# Sheet1.net
KiCad netlist of a schematic drawn in Altium Designer
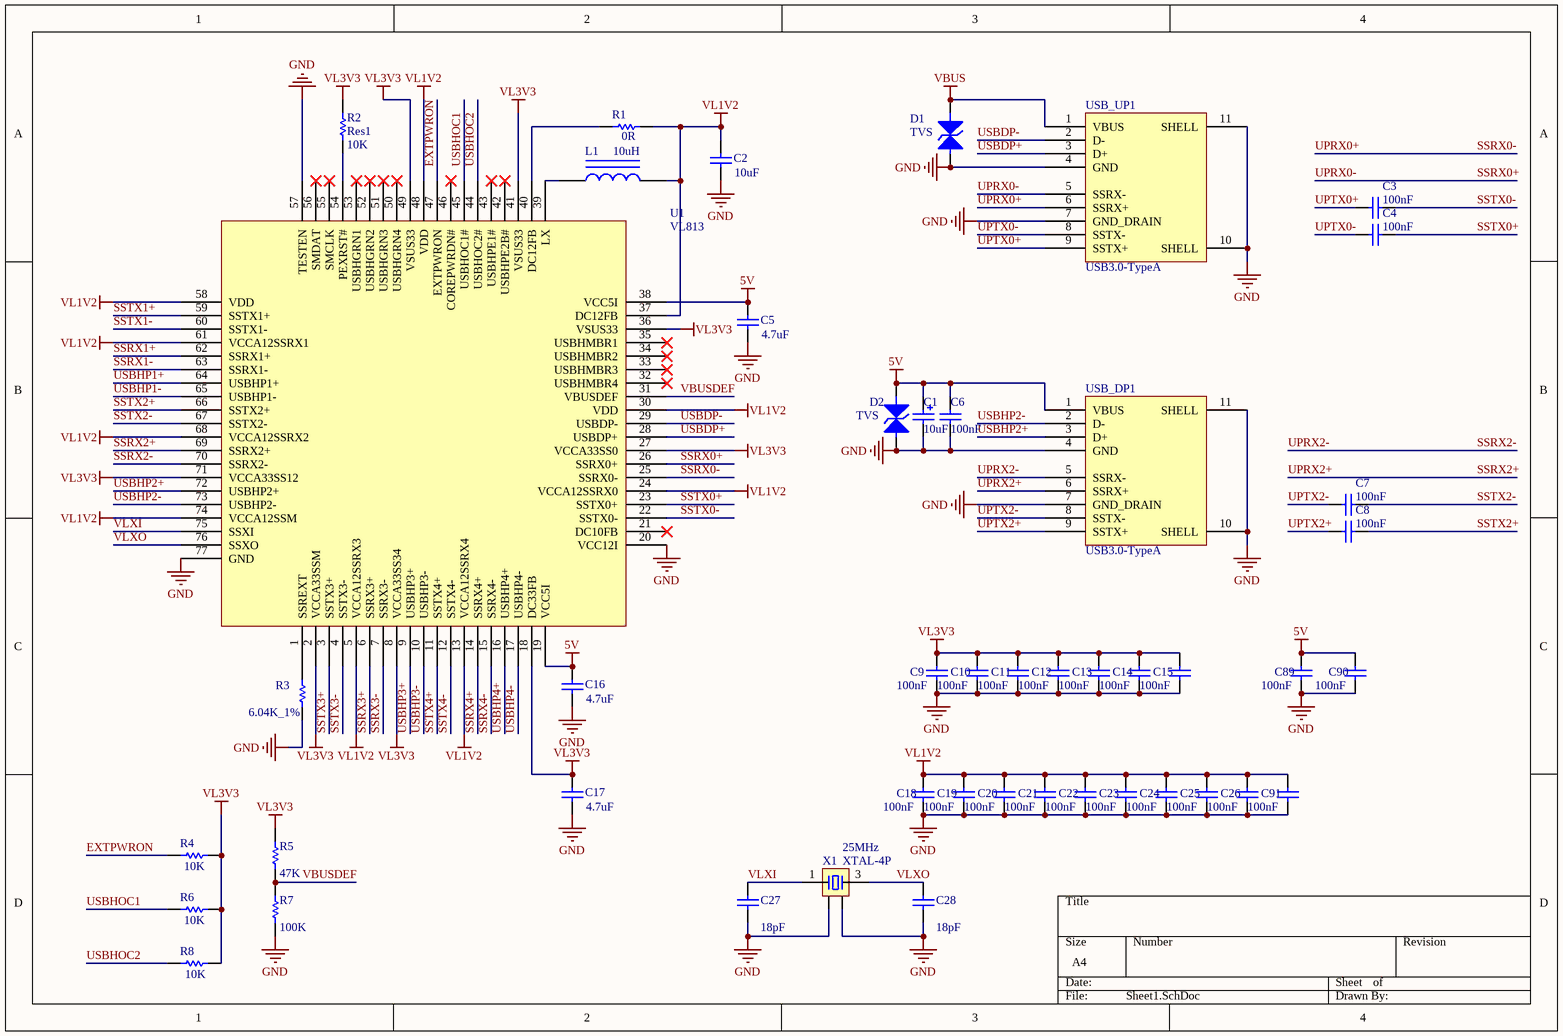
[diagram p0: Sheet1.SchDoc]

(export (version "E")
  (design (tool "Eeschema 10.0.6"))
  (components
    (comp (ref "C1")
      (value "10uF")
      (footprint "电容:TAJ-A/3216")
      (description "Polarized Capacitor (Axial)")
      (fields (field (name "Comment") "Cap Pol2") (field (name "PUBLISHER") "Altium Limited"))
      (libsource (lib "Miscellaneous Devices") (part "Cap Pol2"))
    )
    (comp (ref "C2")
      (value "10uF")
      (footprint "C0603_M")
      (description "Capacitor")
      (fields (field (name "Comment") "Cap") (field (name "PUBLISHER") "Altium Limited"))
      (libsource (lib "Miscellaneous Devices") (part "Cap"))
    )
    (comp (ref "C3")
      (value "100nF")
      (footprint "1.03-电容:C0402_M")
      (description "Capacitor")
      (fields (field (name "Comment") "Cap") (field (name "PUBLISHER") "Altium Limited"))
      (libsource (lib "Miscellaneous Devices") (part "Cap"))
    )
    (comp (ref "C4")
      (value "100nF")
      (footprint "1.03-电容:C0402_M")
      (description "Capacitor")
      (fields (field (name "Comment") "Cap") (field (name "PUBLISHER") "Altium Limited"))
      (libsource (lib "Miscellaneous Devices") (part "Cap"))
    )
    (comp (ref "C5")
      (value "4.7uF")
      (footprint "C0603_M")
      (description "Capacitor")
      (fields (field (name "Comment") "Cap") (field (name "PUBLISHER") "Altium Limited"))
      (libsource (lib "Miscellaneous Devices") (part "Cap"))
    )
    (comp (ref "C6")
      (value "100nF")
      (footprint "C0603_M")
      (description "Capacitor")
      (fields (field (name "Comment") "Cap") (field (name "PUBLISHER") "Altium Limited"))
      (libsource (lib "Miscellaneous Devices") (part "Cap"))
    )
    (comp (ref "C7")
      (value "100nF")
      (footprint "1.03-电容:C0402_M")
      (description "Capacitor")
      (fields (field (name "Comment") "Cap") (field (name "PUBLISHER") "Altium Limited"))
      (libsource (lib "Miscellaneous Devices") (part "Cap"))
    )
    (comp (ref "C8")
      (value "100nF")
      (footprint "1.03-电容:C0402_M")
      (description "Capacitor")
      (fields (field (name "Comment") "Cap") (field (name "PUBLISHER") "Altium Limited"))
      (libsource (lib "Miscellaneous Devices") (part "Cap"))
    )
    (comp (ref "C9")
      (value "100nF")
      (footprint "1.03-电容:C0603_M")
      (description "Capacitor")
      (fields (field (name "Comment") "Cap") (field (name "PUBLISHER") "Altium Limited"))
      (libsource (lib "Miscellaneous Devices") (part "Cap"))
    )
    (comp (ref "C10")
      (value "100nF")
      (footprint "C0603_M")
      (description "Capacitor")
      (fields (field (name "Comment") "Cap") (field (name "PUBLISHER") "Altium Limited"))
      (libsource (lib "Miscellaneous Devices") (part "Cap"))
    )
    (comp (ref "C11")
      (value "100nF")
      (footprint "C0603_M")
      (description "Capacitor")
      (fields (field (name "Comment") "Cap") (field (name "PUBLISHER") "Altium Limited"))
      (libsource (lib "Miscellaneous Devices") (part "Cap"))
    )
    (comp (ref "C12")
      (value "100nF")
      (footprint "C0603_M")
      (description "Capacitor")
      (fields (field (name "Comment") "Cap") (field (name "PUBLISHER") "Altium Limited"))
      (libsource (lib "Miscellaneous Devices") (part "Cap"))
    )
    (comp (ref "C13")
      (value "100nF")
      (footprint "C0603_M")
      (description "Capacitor")
      (fields (field (name "Comment") "Cap") (field (name "PUBLISHER") "Altium Limited"))
      (libsource (lib "Miscellaneous Devices") (part "Cap"))
    )
    (comp (ref "C14")
      (value "100nF")
      (footprint "C0603_M")
      (description "Capacitor")
      (fields (field (name "Comment") "Cap") (field (name "PUBLISHER") "Altium Limited"))
      (libsource (lib "Miscellaneous Devices") (part "Cap"))
    )
    (comp (ref "C15")
      (value "100nF")
      (footprint "C0603_M")
      (description "Capacitor")
      (fields (field (name "Comment") "Cap") (field (name "PUBLISHER") "Altium Limited"))
      (libsource (lib "Miscellaneous Devices") (part "Cap"))
    )
    (comp (ref "C16")
      (value "4.7uF")
      (footprint "C0603_M")
      (description "Capacitor")
      (fields (field (name "Comment") "Cap") (field (name "PUBLISHER") "Altium Limited"))
      (libsource (lib "Miscellaneous Devices") (part "Cap"))
    )
    (comp (ref "C17")
      (value "4.7uF")
      (footprint "C0603_M")
      (description "Capacitor")
      (fields (field (name "Comment") "Cap") (field (name "PUBLISHER") "Altium Limited"))
      (libsource (lib "Miscellaneous Devices") (part "Cap"))
    )
    (comp (ref "C18")
      (value "100nF")
      (footprint "C0603_M")
      (description "Capacitor")
      (fields (field (name "Comment") "Cap") (field (name "PUBLISHER") "Altium Limited"))
      (libsource (lib "Miscellaneous Devices") (part "Cap"))
    )
    (comp (ref "C19")
      (value "100nF")
      (footprint "C0603_M")
      (description "Capacitor")
      (fields (field (name "Comment") "Cap") (field (name "PUBLISHER") "Altium Limited"))
      (libsource (lib "Miscellaneous Devices") (part "Cap"))
    )
    (comp (ref "C20")
      (value "100nF")
      (footprint "C0603_M")
      (description "Capacitor")
      (fields (field (name "Comment") "Cap") (field (name "PUBLISHER") "Altium Limited"))
      (libsource (lib "Miscellaneous Devices") (part "Cap"))
    )
    (comp (ref "C21")
      (value "100nF")
      (footprint "C0603_M")
      (description "Capacitor")
      (fields (field (name "Comment") "Cap") (field (name "PUBLISHER") "Altium Limited"))
      (libsource (lib "Miscellaneous Devices") (part "Cap"))
    )
    (comp (ref "C22")
      (value "100nF")
      (footprint "C0603_M")
      (description "Capacitor")
      (fields (field (name "Comment") "Cap") (field (name "PUBLISHER") "Altium Limited"))
      (libsource (lib "Miscellaneous Devices") (part "Cap"))
    )
    (comp (ref "C23")
      (value "100nF")
      (footprint "C0603_M")
      (description "Capacitor")
      (fields (field (name "Comment") "Cap") (field (name "PUBLISHER") "Altium Limited"))
      (libsource (lib "Miscellaneous Devices") (part "Cap"))
    )
    (comp (ref "C24")
      (value "100nF")
      (footprint "C0603_M")
      (description "Capacitor")
      (fields (field (name "Comment") "Cap") (field (name "PUBLISHER") "Altium Limited"))
      (libsource (lib "Miscellaneous Devices") (part "Cap"))
    )
    (comp (ref "C25")
      (value "100nF")
      (footprint "C0603_M")
      (description "Capacitor")
      (fields (field (name "Comment") "Cap") (field (name "PUBLISHER") "Altium Limited"))
      (libsource (lib "Miscellaneous Devices") (part "Cap"))
    )
    (comp (ref "C26")
      (value "100nF")
      (footprint "C0603_M")
      (description "Capacitor")
      (fields (field (name "Comment") "Cap") (field (name "PUBLISHER") "Altium Limited"))
      (libsource (lib "Miscellaneous Devices") (part "Cap"))
    )
    (comp (ref "C27")
      (value "18pF")
      (footprint "C0603_M")
      (description "Capacitor")
      (fields (field (name "Comment") "Cap") (field (name "PUBLISHER") "Altium Limited"))
      (libsource (lib "Miscellaneous Devices") (part "Cap"))
    )
    (comp (ref "C28")
      (value "18pF")
      (footprint "C0603_M")
      (description "Capacitor")
      (fields (field (name "Comment") "Cap") (field (name "PUBLISHER") "Altium Limited"))
      (libsource (lib "Miscellaneous Devices") (part "Cap"))
    )
    (comp (ref "C89")
      (value "100nF")
      (footprint "C0603_M")
      (description "Capacitor")
      (fields (field (name "Comment") "Cap") (field (name "PUBLISHER") "Altium Limited"))
      (libsource (lib "Miscellaneous Devices") (part "Cap"))
    )
    (comp (ref "C90")
      (value "100nF")
      (footprint "C0603_M")
      (description "Capacitor")
      (fields (field (name "Comment") "Cap") (field (name "PUBLISHER") "Altium Limited"))
      (libsource (lib "Miscellaneous Devices") (part "Cap"))
    )
    (comp (ref "C91")
      (value "100nF")
      (footprint "C0603_M")
      (description "Capacitor")
      (fields (field (name "Comment") "Cap") (field (name "PUBLISHER") "Altium Limited"))
      (libsource (lib "Miscellaneous Devices") (part "Cap"))
    )
    (comp (ref "D1")
      (value "TVS")
      (footprint "二极管:SOD-123")
      (description "双向瞬态抑制二极管")
      (libsource (lib "二极管") (part "TVS"))
    )
    (comp (ref "D2")
      (value "TVS")
      (footprint "二极管:SOD-123")
      (description "双向瞬态抑制二极管")
      (libsource (lib "二极管") (part "TVS"))
    )
    (comp (ref "L1")
      (value "10uH")
      (footprint "1.04-电感:SWPA3012")
      (description "Magnetic-Core Inductor")
      (fields (field (name "Comment") "Inductor Iron") (field (name "PUBLISHER") "Altium Limited"))
      (libsource (lib "Miscellaneous Devices") (part "Inductor Iron"))
    )
    (comp (ref "R1")
      (value "0R")
      (footprint "R0603_M")
      (description "Resistor")
      (fields (field (name "Comment") "Res1") (field (name "PUBLISHER") "Altium Limited"))
      (libsource (lib "Miscellaneous Devices") (part "Res1"))
    )
    (comp (ref "R2")
      (value "Res1")
      (footprint "R0603_M")
      (description "Resistor")
      (fields (field (name "ALTIUM_VALUE") "10K") (field (name "PUBLISHER") "Altium Limited"))
      (libsource (lib "Miscellaneous Devices") (part "Res1"))
    )
    (comp (ref "R3")
      (value "6.04K_1%")
      (footprint "R0603_M")
      (description "Resistor")
      (fields (field (name "Comment") "Res1") (field (name "PUBLISHER") "Altium Limited"))
      (libsource (lib "Miscellaneous Devices") (part "Res1"))
    )
    (comp (ref "R4")
      (value "10K")
      (footprint "R0603_M")
      (description "Resistor")
      (fields (field (name "Comment") "Res1") (field (name "PUBLISHER") "Altium Limited"))
      (libsource (lib "Miscellaneous Devices") (part "Res1"))
    )
    (comp (ref "R5")
      (value "47K")
      (footprint "R0603_M")
      (description "Resistor")
      (fields (field (name "Comment") "Res1") (field (name "PUBLISHER") "Altium Limited"))
      (libsource (lib "Miscellaneous Devices") (part "Res1"))
    )
    (comp (ref "R6")
      (value "10K")
      (footprint "R0603_M")
      (description "Resistor")
      (fields (field (name "Comment") "Res1") (field (name "PUBLISHER") "Altium Limited"))
      (libsource (lib "Miscellaneous Devices") (part "Res1"))
    )
    (comp (ref "R7")
      (value "100K")
      (footprint "R0603_M")
      (description "Resistor")
      (fields (field (name "Comment") "Res1") (field (name "PUBLISHER") "Altium Limited"))
      (libsource (lib "Miscellaneous Devices") (part "Res1"))
    )
    (comp (ref "R8")
      (value "10K")
      (footprint "R0603_M")
      (description "Resistor")
      (fields (field (name "Comment") "Res1") (field (name "PUBLISHER") "Altium Limited"))
      (libsource (lib "Miscellaneous Devices") (part "Res1"))
    )
    (comp (ref "U1")
      (value "VL813")
      (footprint "QFN-76_L9.0-W9.0")
      (description "USB3.0 Hub")
      (libsource (lib "MyIntLib") (part "VL813"))
    )
    (comp (ref "USB_DP1")
      (value "USB3.0-TypeA")
      (footprint "3.03-USB3.1 Type C-M.2-NGFF-HDMI-PCI-E接口:USB3.1 Type-A_DIP_F")
      (libsource (lib "MyIntLib") (part "USB3.0-TypeA"))
    )
    (comp (ref "USB_UP1")
      (value "USB3.0-TypeA")
      (footprint "3.03-USB3.1 Type C-M.2-NGFF-HDMI-PCI-E接口:USB3.1 Type-A_DIP_F")
      (libsource (lib "MyIntLib") (part "USB3.0-TypeA"))
    )
    (comp (ref "X1")
      (value "XTAL-4P")
      (footprint "OSC 3225-4P")
      (description "4脚无源晶振")
      (fields (field (name "PARAMETER 1") "25MHz"))
      (libsource (lib "晶振") (part "XTAL-4P"))
    )
  )
  (nets
    (net (code "1") (name "/EXTPWRON") (class "Default")
      (node (ref "R4") (pin "2") (pinfunction "2_2") (pintype "passive"))
      (node (ref "U1") (pin "47") (pinfunction "EXTPWRON_47") (pintype "passive"))
    )
    (net (code "2") (name "/SSRX0+") (class "Default")
      (node (ref "U1") (pin "26") (pinfunction "SSRX0+_26") (pintype "passive"))
      (node (ref "USB_UP1") (pin "5") (pinfunction "SSRX-_5") (pintype "passive"))
    )
    (net (code "3") (name "/SSRX0-") (class "Default")
      (node (ref "U1") (pin "25") (pinfunction "SSRX0-_25") (pintype "passive"))
      (node (ref "USB_UP1") (pin "6") (pinfunction "SSRX+_6") (pintype "passive"))
    )
    (net (code "4") (name "/SSRX1+") (class "Default")
      (node (ref "U1") (pin "62") (pinfunction "SSRX1+_62") (pintype "passive"))
    )
    (net (code "5") (name "/SSRX1-") (class "Default")
      (node (ref "U1") (pin "63") (pinfunction "SSRX1-_63") (pintype "passive"))
    )
    (net (code "6") (name "/SSRX2+") (class "Default")
      (node (ref "U1") (pin "69") (pinfunction "SSRX2+_69") (pintype "passive"))
      (node (ref "USB_DP1") (pin "6") (pinfunction "SSRX+_6") (pintype "passive"))
    )
    (net (code "7") (name "/SSRX2-") (class "Default")
      (node (ref "U1") (pin "70") (pinfunction "SSRX2-_70") (pintype "passive"))
      (node (ref "USB_DP1") (pin "5") (pinfunction "SSRX-_5") (pintype "passive"))
    )
    (net (code "8") (name "/SSRX3+") (class "Default")
      (node (ref "U1") (pin "6") (pinfunction "SSRX3+_6") (pintype "passive"))
    )
    (net (code "9") (name "/SSRX3-") (class "Default")
      (node (ref "U1") (pin "7") (pinfunction "SSRX3-_7") (pintype "passive"))
    )
    (net (code "10") (name "/SSRX4+") (class "Default")
      (node (ref "U1") (pin "14") (pinfunction "SSRX4+_14") (pintype "passive"))
    )
    (net (code "11") (name "/SSRX4-") (class "Default")
      (node (ref "U1") (pin "15") (pinfunction "SSRX4-_15") (pintype "passive"))
    )
    (net (code "12") (name "/SSTX0+") (class "Default")
      (node (ref "C4") (pin "1") (pinfunction "1_1") (pintype "passive"))
      (node (ref "U1") (pin "23") (pinfunction "SSTX0+_23") (pintype "passive"))
    )
    (net (code "13") (name "/SSTX0-") (class "Default")
      (node (ref "C3") (pin "1") (pinfunction "1_1") (pintype "passive"))
      (node (ref "U1") (pin "22") (pinfunction "SSTX0-_22") (pintype "passive"))
    )
    (net (code "14") (name "/SSTX1+") (class "Default")
      (node (ref "U1") (pin "59") (pinfunction "SSTX1+_59") (pintype "passive"))
    )
    (net (code "15") (name "/SSTX1-") (class "Default")
      (node (ref "U1") (pin "60") (pinfunction "SSTX1-_60") (pintype "passive"))
    )
    (net (code "16") (name "/SSTX2+") (class "Default")
      (node (ref "C8") (pin "1") (pinfunction "1_1") (pintype "passive"))
      (node (ref "U1") (pin "66") (pinfunction "SSTX2+_66") (pintype "passive"))
    )
    (net (code "17") (name "/SSTX2-") (class "Default")
      (node (ref "C7") (pin "1") (pinfunction "1_1") (pintype "passive"))
      (node (ref "U1") (pin "67") (pinfunction "SSTX2-_67") (pintype "passive"))
    )
    (net (code "18") (name "/SSTX3+") (class "Default")
      (node (ref "U1") (pin "3") (pinfunction "SSTX3+_3") (pintype "passive"))
    )
    (net (code "19") (name "/SSTX3-") (class "Default")
      (node (ref "U1") (pin "4") (pinfunction "SSTX3-_4") (pintype "passive"))
    )
    (net (code "20") (name "/SSTX4+") (class "Default")
      (node (ref "U1") (pin "11") (pinfunction "SSTX4+_11") (pintype "passive"))
    )
    (net (code "21") (name "/SSTX4-") (class "Default")
      (node (ref "U1") (pin "12") (pinfunction "SSTX4-_12") (pintype "passive"))
    )
    (net (code "22") (name "/UPTX0+") (class "Default")
      (node (ref "C3") (pin "2") (pinfunction "2_2") (pintype "passive"))
      (node (ref "USB_UP1") (pin "9") (pinfunction "SSTX+_9") (pintype "passive"))
    )
    (net (code "23") (name "/UPTX0-") (class "Default")
      (node (ref "C4") (pin "2") (pinfunction "2_2") (pintype "passive"))
      (node (ref "USB_UP1") (pin "8") (pinfunction "SSTX-_8") (pintype "passive"))
    )
    (net (code "24") (name "/UPTX2+") (class "Default")
      (node (ref "C8") (pin "2") (pinfunction "2_2") (pintype "passive"))
      (node (ref "USB_DP1") (pin "9") (pinfunction "SSTX+_9") (pintype "passive"))
    )
    (net (code "25") (name "/UPTX2-") (class "Default")
      (node (ref "C7") (pin "2") (pinfunction "2_2") (pintype "passive"))
      (node (ref "USB_DP1") (pin "8") (pinfunction "SSTX-_8") (pintype "passive"))
    )
    (net (code "26") (name "/USBDP+") (class "Default")
      (node (ref "U1") (pin "28") (pinfunction "USBDP+_28") (pintype "passive"))
      (node (ref "USB_UP1") (pin "3") (pinfunction "D+_3") (pintype "passive"))
    )
    (net (code "27") (name "/USBDP-") (class "Default")
      (node (ref "U1") (pin "29") (pinfunction "USBDP-_29") (pintype "passive"))
      (node (ref "USB_UP1") (pin "2") (pinfunction "D-_2") (pintype "passive"))
    )
    (net (code "28") (name "/USBHOC1") (class "Default")
      (node (ref "R6") (pin "2") (pinfunction "2_2") (pintype "passive"))
      (node (ref "U1") (pin "45") (pinfunction "USBHOC1#_45") (pintype "passive"))
    )
    (net (code "29") (name "/USBHOC2") (class "Default")
      (node (ref "R8") (pin "2") (pinfunction "2_2") (pintype "passive"))
      (node (ref "U1") (pin "44") (pinfunction "USBHOC2#_44") (pintype "passive"))
    )
    (net (code "30") (name "/USBHP1+") (class "Default")
      (node (ref "U1") (pin "64") (pinfunction "USBHP1+_64") (pintype "passive"))
    )
    (net (code "31") (name "/USBHP1-") (class "Default")
      (node (ref "U1") (pin "65") (pinfunction "USBHP1-_65") (pintype "passive"))
    )
    (net (code "32") (name "/USBHP2+") (class "Default")
      (node (ref "U1") (pin "72") (pinfunction "USBHP2+_72") (pintype "passive"))
      (node (ref "USB_DP1") (pin "3") (pinfunction "D+_3") (pintype "passive"))
    )
    (net (code "33") (name "/USBHP2-") (class "Default")
      (node (ref "U1") (pin "73") (pinfunction "USBHP2-_73") (pintype "passive"))
      (node (ref "USB_DP1") (pin "2") (pinfunction "D-_2") (pintype "passive"))
    )
    (net (code "34") (name "/USBHP3+") (class "Default")
      (node (ref "U1") (pin "9") (pinfunction "USBHP3+_9") (pintype "passive"))
    )
    (net (code "35") (name "/USBHP3-") (class "Default")
      (node (ref "U1") (pin "10") (pinfunction "USBHP3-_10") (pintype "passive"))
    )
    (net (code "36") (name "/USBHP4+") (class "Default")
      (node (ref "U1") (pin "16") (pinfunction "USBHP4+_16") (pintype "passive"))
    )
    (net (code "37") (name "/USBHP4-") (class "Default")
      (node (ref "U1") (pin "17") (pinfunction "USBHP4-_17") (pintype "passive"))
    )
    (net (code "38") (name "/VBUSDEF") (class "Default")
      (node (ref "R5") (pin "1") (pinfunction "1_1") (pintype "passive"))
      (node (ref "R7") (pin "2") (pinfunction "2_2") (pintype "passive"))
      (node (ref "U1") (pin "31") (pinfunction "VBUSDEF_31") (pintype "passive"))
    )
    (net (code "39") (name "/VLXI") (class "Default")
      (node (ref "C27") (pin "1") (pinfunction "1_1") (pintype "passive"))
      (node (ref "U1") (pin "75") (pinfunction "SSXI_75") (pintype "passive"))
      (node (ref "X1") (pin "1") (pinfunction "1_1") (pintype "passive"))
    )
    (net (code "40") (name "/VLXO") (class "Default")
      (node (ref "C28") (pin "1") (pinfunction "1_1") (pintype "passive"))
      (node (ref "U1") (pin "76") (pinfunction "SSXO_76") (pintype "passive"))
      (node (ref "X1") (pin "3") (pinfunction "3_3") (pintype "passive"))
    )
    (net (code "41") (name "5V") (class "Default")
      (node (ref "C1") (pin "1") (pinfunction "1_1") (pintype "passive"))
      (node (ref "C16") (pin "2") (pinfunction "2_2") (pintype "passive"))
      (node (ref "C5") (pin "2") (pinfunction "2_2") (pintype "passive"))
      (node (ref "C6") (pin "1") (pinfunction "1_1") (pintype "passive"))
      (node (ref "C89") (pin "1") (pinfunction "1_1") (pintype "passive"))
      (node (ref "C90") (pin "1") (pinfunction "1_1") (pintype "passive"))
      (node (ref "D2") (pin "K") (pinfunction "K_K") (pintype "passive"))
      (node (ref "U1") (pin "19") (pinfunction "VCC5I_19") (pintype "passive"))
      (node (ref "U1") (pin "38") (pinfunction "VCC5I_38") (pintype "passive"))
      (node (ref "USB_DP1") (pin "1") (pinfunction "VBUS_1") (pintype "passive"))
    )
    (net (code "42") (name "GND") (class "Default")
      (node (ref "C1") (pin "2") (pinfunction "2_2") (pintype "passive"))
      (node (ref "C10") (pin "2") (pinfunction "2_2") (pintype "passive"))
      (node (ref "C11") (pin "2") (pinfunction "2_2") (pintype "passive"))
      (node (ref "C12") (pin "2") (pinfunction "2_2") (pintype "passive"))
      (node (ref "C13") (pin "2") (pinfunction "2_2") (pintype "passive"))
      (node (ref "C14") (pin "2") (pinfunction "2_2") (pintype "passive"))
      (node (ref "C15") (pin "2") (pinfunction "2_2") (pintype "passive"))
      (node (ref "C16") (pin "1") (pinfunction "1_1") (pintype "passive"))
      (node (ref "C17") (pin "1") (pinfunction "1_1") (pintype "passive"))
      (node (ref "C18") (pin "2") (pinfunction "2_2") (pintype "passive"))
      (node (ref "C19") (pin "2") (pinfunction "2_2") (pintype "passive"))
      (node (ref "C2") (pin "1") (pinfunction "1_1") (pintype "passive"))
      (node (ref "C20") (pin "2") (pinfunction "2_2") (pintype "passive"))
      (node (ref "C21") (pin "2") (pinfunction "2_2") (pintype "passive"))
      (node (ref "C22") (pin "2") (pinfunction "2_2") (pintype "passive"))
      (node (ref "C23") (pin "2") (pinfunction "2_2") (pintype "passive"))
      (node (ref "C24") (pin "2") (pinfunction "2_2") (pintype "passive"))
      (node (ref "C25") (pin "2") (pinfunction "2_2") (pintype "passive"))
      (node (ref "C26") (pin "2") (pinfunction "2_2") (pintype "passive"))
      (node (ref "C27") (pin "2") (pinfunction "2_2") (pintype "passive"))
      (node (ref "C28") (pin "2") (pinfunction "2_2") (pintype "passive"))
      (node (ref "C5") (pin "1") (pinfunction "1_1") (pintype "passive"))
      (node (ref "C6") (pin "2") (pinfunction "2_2") (pintype "passive"))
      (node (ref "C89") (pin "2") (pinfunction "2_2") (pintype "passive"))
      (node (ref "C9") (pin "2") (pinfunction "2_2") (pintype "passive"))
      (node (ref "C90") (pin "2") (pinfunction "2_2") (pintype "passive"))
      (node (ref "C91") (pin "2") (pinfunction "2_2") (pintype "passive"))
      (node (ref "D1") (pin "A") (pinfunction "A_A") (pintype "passive"))
      (node (ref "D2") (pin "A") (pinfunction "A_A") (pintype "passive"))
      (node (ref "R3") (pin "1") (pinfunction "1_1") (pintype "passive"))
      (node (ref "R7") (pin "1") (pinfunction "1_1") (pintype "passive"))
      (node (ref "U1") (pin "20") (pinfunction "VCC12I_20") (pintype "passive"))
      (node (ref "U1") (pin "57") (pinfunction "TESTEN_57") (pintype "passive"))
      (node (ref "U1") (pin "77") (pinfunction "GND_77") (pintype "passive"))
      (node (ref "USB_DP1") (pin "10") (pinfunction "SHELL_10") (pintype "passive"))
      (node (ref "USB_DP1") (pin "11") (pinfunction "SHELL_11") (pintype "passive"))
      (node (ref "USB_DP1") (pin "4") (pinfunction "GND_4") (pintype "passive"))
      (node (ref "USB_DP1") (pin "7") (pinfunction "GND_DRAIN_7") (pintype "passive"))
      (node (ref "USB_UP1") (pin "10") (pinfunction "SHELL_10") (pintype "passive"))
      (node (ref "USB_UP1") (pin "11") (pinfunction "SHELL_11") (pintype "passive"))
      (node (ref "USB_UP1") (pin "4") (pinfunction "GND_4") (pintype "passive"))
      (node (ref "USB_UP1") (pin "7") (pinfunction "GND_DRAIN_7") (pintype "passive"))
      (node (ref "X1") (pin "2") (pinfunction "2_2") (pintype "passive"))
      (node (ref "X1") (pin "4") (pinfunction "4_4") (pintype "passive"))
    )
    (net (code "43") (name "Net-(R1-Pad1)") (class "Default")
      (node (ref "R1") (pin "1") (pinfunction "1_1") (pintype "passive"))
      (node (ref "U1") (pin "40") (pinfunction "DC12FB_40") (pintype "passive"))
    )
    (net (code "44") (name "Net-(U1-LX)") (class "Default")
      (node (ref "L1") (pin "1") (pinfunction "1_1") (pintype "passive"))
      (node (ref "U1") (pin "39") (pinfunction "LX_39") (pintype "passive"))
    )
    (net (code "45") (name "Net-(U1-PEXRST#)") (class "Default")
      (node (ref "R2") (pin "1") (pinfunction "1_1") (pintype "passive"))
      (node (ref "U1") (pin "54") (pinfunction "PEXRST#_54") (pintype "passive"))
    )
    (net (code "46") (name "Net-(U1-SSREXT)") (class "Default")
      (node (ref "R3") (pin "2") (pinfunction "2_2") (pintype "passive"))
      (node (ref "U1") (pin "1") (pinfunction "SSREXT_1") (pintype "passive"))
    )
    (net (code "47") (name "VBUS") (class "Default")
      (node (ref "D1") (pin "K") (pinfunction "K_K") (pintype "passive"))
      (node (ref "USB_UP1") (pin "1") (pinfunction "VBUS_1") (pintype "passive"))
    )
    (net (code "48") (name "VL1V2") (class "Default")
      (node (ref "C18") (pin "1") (pinfunction "1_1") (pintype "passive"))
      (node (ref "C19") (pin "1") (pinfunction "1_1") (pintype "passive"))
      (node (ref "C2") (pin "2") (pinfunction "2_2") (pintype "passive"))
      (node (ref "C20") (pin "1") (pinfunction "1_1") (pintype "passive"))
      (node (ref "C21") (pin "1") (pinfunction "1_1") (pintype "passive"))
      (node (ref "C22") (pin "1") (pinfunction "1_1") (pintype "passive"))
      (node (ref "C23") (pin "1") (pinfunction "1_1") (pintype "passive"))
      (node (ref "C24") (pin "1") (pinfunction "1_1") (pintype "passive"))
      (node (ref "C25") (pin "1") (pinfunction "1_1") (pintype "passive"))
      (node (ref "C26") (pin "1") (pinfunction "1_1") (pintype "passive"))
      (node (ref "C91") (pin "1") (pinfunction "1_1") (pintype "passive"))
      (node (ref "L1") (pin "2") (pinfunction "2_2") (pintype "passive"))
      (node (ref "R1") (pin "2") (pinfunction "2_2") (pintype "passive"))
      (node (ref "U1") (pin "13") (pinfunction "VCCA12SSRX4_13") (pintype "passive"))
      (node (ref "U1") (pin "24") (pinfunction "VCCA12SSRX0_24") (pintype "passive"))
      (node (ref "U1") (pin "30") (pinfunction "VDD_30") (pintype "passive"))
      (node (ref "U1") (pin "37") (pinfunction "DC12FB_37") (pintype "passive"))
      (node (ref "U1") (pin "48") (pinfunction "VDD_48") (pintype "passive"))
      (node (ref "U1") (pin "5") (pinfunction "VCCA12SSRX3_5") (pintype "passive"))
      (node (ref "U1") (pin "58") (pinfunction "VDD_58") (pintype "passive"))
      (node (ref "U1") (pin "61") (pinfunction "VCCA12SSRX1_61") (pintype "passive"))
      (node (ref "U1") (pin "68") (pinfunction "VCCA12SSRX2_68") (pintype "passive"))
      (node (ref "U1") (pin "74") (pinfunction "VCCA12SSM_74") (pintype "passive"))
    )
    (net (code "49") (name "VL3V3") (class "Default")
      (node (ref "C10") (pin "1") (pinfunction "1_1") (pintype "passive"))
      (node (ref "C11") (pin "1") (pinfunction "1_1") (pintype "passive"))
      (node (ref "C12") (pin "1") (pinfunction "1_1") (pintype "passive"))
      (node (ref "C13") (pin "1") (pinfunction "1_1") (pintype "passive"))
      (node (ref "C14") (pin "1") (pinfunction "1_1") (pintype "passive"))
      (node (ref "C15") (pin "1") (pinfunction "1_1") (pintype "passive"))
      (node (ref "C17") (pin "2") (pinfunction "2_2") (pintype "passive"))
      (node (ref "C9") (pin "1") (pinfunction "1_1") (pintype "passive"))
      (node (ref "R2") (pin "2") (pinfunction "2_2") (pintype "passive"))
      (node (ref "R4") (pin "1") (pinfunction "1_1") (pintype "passive"))
      (node (ref "R5") (pin "2") (pinfunction "2_2") (pintype "passive"))
      (node (ref "R6") (pin "1") (pinfunction "1_1") (pintype "passive"))
      (node (ref "R8") (pin "1") (pinfunction "1_1") (pintype "passive"))
      (node (ref "U1") (pin "18") (pinfunction "DC33FB_18") (pintype "passive"))
      (node (ref "U1") (pin "2") (pinfunction "VCCA33SSM_2") (pintype "passive"))
      (node (ref "U1") (pin "27") (pinfunction "VCCA33SS0_27") (pintype "passive"))
      (node (ref "U1") (pin "36") (pinfunction "VSUS33_36") (pintype "passive"))
      (node (ref "U1") (pin "41") (pinfunction "VSUS33_41") (pintype "passive"))
      (node (ref "U1") (pin "49") (pinfunction "VSUS33_49") (pintype "passive"))
      (node (ref "U1") (pin "71") (pinfunction "VCCA33SS12_71") (pintype "passive"))
      (node (ref "U1") (pin "8") (pinfunction "VCCA33SS34_8") (pintype "passive"))
    )
    (net (code "50") (name "unconnected-(U1-COREPWRDN#-Pad46)") (class "Default")
      (node (ref "U1") (pin "46") (pinfunction "COREPWRDN#_46") (pintype "passive+no_connect"))
    )
    (net (code "51") (name "unconnected-(U1-DC10FB-Pad21)") (class "Default")
      (node (ref "U1") (pin "21") (pinfunction "DC10FB_21") (pintype "passive+no_connect"))
    )
    (net (code "52") (name "unconnected-(U1-SMCLK-Pad55)") (class "Default")
      (node (ref "U1") (pin "55") (pinfunction "SMCLK_55") (pintype "passive+no_connect"))
    )
    (net (code "53") (name "unconnected-(U1-SMDAT-Pad56)") (class "Default")
      (node (ref "U1") (pin "56") (pinfunction "SMDAT_56") (pintype "passive+no_connect"))
    )
    (net (code "54") (name "unconnected-(U1-USBHGRN1-Pad53)") (class "Default")
      (node (ref "U1") (pin "53") (pinfunction "USBHGRN1_53") (pintype "passive+no_connect"))
    )
    (net (code "55") (name "unconnected-(U1-USBHGRN2-Pad52)") (class "Default")
      (node (ref "U1") (pin "52") (pinfunction "USBHGRN2_52") (pintype "passive+no_connect"))
    )
    (net (code "56") (name "unconnected-(U1-USBHGRN3-Pad51)") (class "Default")
      (node (ref "U1") (pin "51") (pinfunction "USBHGRN3_51") (pintype "passive+no_connect"))
    )
    (net (code "57") (name "unconnected-(U1-USBHGRN4-Pad50)") (class "Default")
      (node (ref "U1") (pin "50") (pinfunction "USBHGRN4_50") (pintype "passive+no_connect"))
    )
    (net (code "58") (name "unconnected-(U1-USBHMBR1-Pad35)") (class "Default")
      (node (ref "U1") (pin "35") (pinfunction "USBHMBR1_35") (pintype "passive+no_connect"))
    )
    (net (code "59") (name "unconnected-(U1-USBHMBR2-Pad34)") (class "Default")
      (node (ref "U1") (pin "34") (pinfunction "USBHMBR2_34") (pintype "passive+no_connect"))
    )
    (net (code "60") (name "unconnected-(U1-USBHMBR3-Pad33)") (class "Default")
      (node (ref "U1") (pin "33") (pinfunction "USBHMBR3_33") (pintype "passive+no_connect"))
    )
    (net (code "61") (name "unconnected-(U1-USBHMBR4-Pad32)") (class "Default")
      (node (ref "U1") (pin "32") (pinfunction "USBHMBR4_32") (pintype "passive+no_connect"))
    )
    (net (code "62") (name "unconnected-(U1-USBHPE1#-Pad43)") (class "Default")
      (node (ref "U1") (pin "43") (pinfunction "USBHPE1#_43") (pintype "passive+no_connect"))
    )
    (net (code "63") (name "unconnected-(U1-USBHPE2B#-Pad42)") (class "Default")
      (node (ref "U1") (pin "42") (pinfunction "USBHPE2B#_42") (pintype "passive+no_connect"))
    )
  )
)
